# sch1.net
KiCad netlist of a schematic drawn in Altium Designer
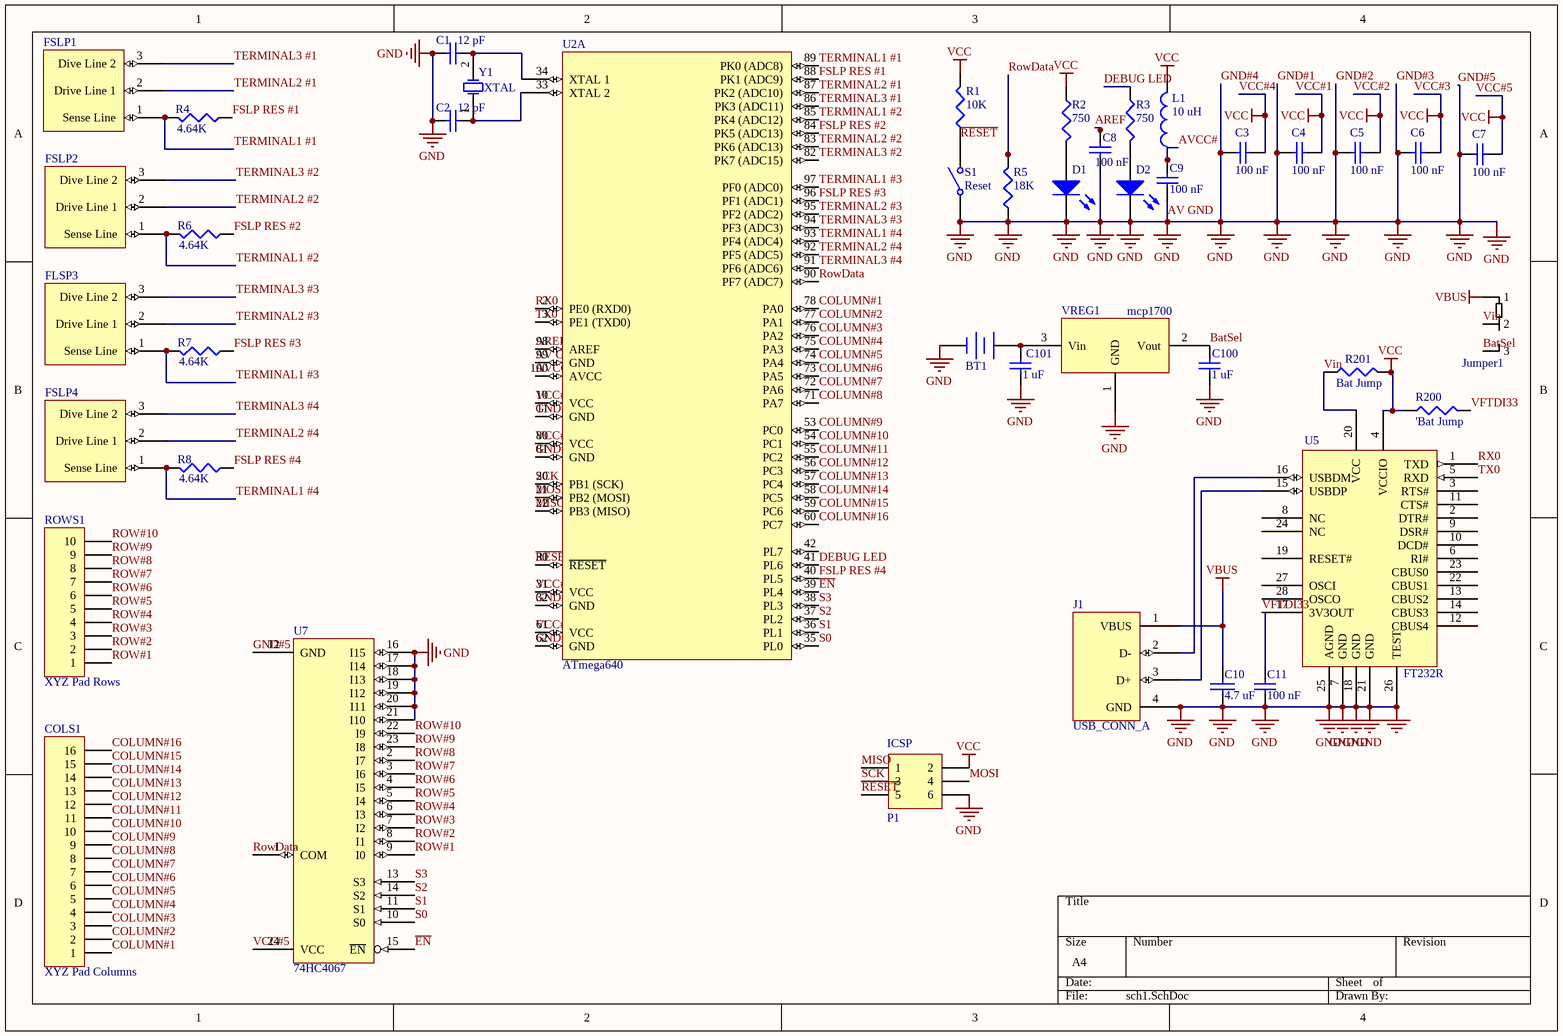
[diagram p0: sch1.SchDoc]

(export (version "E")
  (design (tool "Eeschema 10.0.6"))
  (components
    (comp (ref "BT1")
      (value "Battery 3.7V Li-Ion")
      (footprint "BAT-2")
      (description "Multicell Battery")
      (fields (field (name "PUBLISHER") "Altium Limited"))
      (libsource (lib "Miscellaneous Devices") (part "Battery"))
    )
    (comp (ref "C1")
      (value "12 pF")
      (footprint "0805")
      (description "Capacitor")
      (fields (field (name "PART NUMBER") "311-1100-1-ND") (field (name "MANUFACTURER") "Yageo"))
      (libsource (lib "Miscellaneous Devices") (part "Cap"))
    )
    (comp (ref "C2")
      (value "12 pF")
      (footprint "0805")
      (description "Capacitor")
      (fields (field (name "PART NUMBER") "311-1100-1-ND") (field (name "MANUFACTURER") "Yageo"))
      (libsource (lib "Miscellaneous Devices") (part "Cap"))
    )
    (comp (ref "C3")
      (value "100 nF")
      (footprint "1608[0603]")
      (description "Capacitor")
      (fields (field (name "PART NUMBER") "311-1088-1-ND") (field (name "MANUFACTURER") "Yageo"))
      (libsource (lib "Miscellaneous Devices") (part "Cap"))
    )
    (comp (ref "C4")
      (value "100 nF")
      (footprint "1608[0603]")
      (description "Capacitor")
      (fields (field (name "PART NUMBER") "311-1088-1-ND") (field (name "MANUFACTURER") "Yageo"))
      (libsource (lib "Miscellaneous Devices") (part "Cap"))
    )
    (comp (ref "C5")
      (value "100 nF")
      (footprint "1608[0603]")
      (description "Capacitor")
      (fields (field (name "PART NUMBER") "311-1088-1-ND") (field (name "MANUFACTURER") "Yageo"))
      (libsource (lib "Miscellaneous Devices") (part "Cap"))
    )
    (comp (ref "C6")
      (value "100 nF")
      (footprint "1608[0603]")
      (description "Capacitor")
      (fields (field (name "PART NUMBER") "311-1088-1-ND") (field (name "MANUFACTURER") "Yageo"))
      (libsource (lib "Miscellaneous Devices") (part "Cap"))
    )
    (comp (ref "C7")
      (value "100 nF")
      (footprint "1608[0603]")
      (description "Capacitor")
      (fields (field (name "PART NUMBER") "311-1088-1-ND") (field (name "MANUFACTURER") "Yageo"))
      (libsource (lib "Miscellaneous Devices") (part "Cap"))
    )
    (comp (ref "C8")
      (value "100 nF")
      (footprint "1608[0603]")
      (description "Capacitor")
      (fields (field (name "PART NUMBER") "311-1088-1-ND") (field (name "MANUFACTURER") "Yageo"))
      (libsource (lib "Miscellaneous Devices") (part "Cap"))
    )
    (comp (ref "C9")
      (value "100 nF")
      (footprint "1608[0603]")
      (description "Capacitor")
      (fields (field (name "PART NUMBER") "311-1088-1-ND") (field (name "MANUFACTURER") "Yageo"))
      (libsource (lib "Miscellaneous Devices") (part "Cap"))
    )
    (comp (ref "C10")
      (value "4.7 uF")
      (footprint "1608[0603]")
      (description "Capacitor")
      (fields (field (name "PART NUMBER") "311-1521-1-ND"))
      (libsource (lib "*") (part "CAP"))
    )
    (comp (ref "C11")
      (value "100 nF")
      (footprint "1608[0603]")
      (description "Capacitor")
      (fields (field (name "PART NUMBER") "311-1088-1-ND") (field (name "MANUFACTURER") "Yageo"))
      (libsource (lib "Miscellaneous Devices") (part "Cap"))
    )
    (comp (ref "C100")
      (value "1 uF")
      (footprint "0805")
      (description "Capacitor")
      (libsource (lib "Miscellaneous Devices") (part "Cap"))
    )
    (comp (ref "C101")
      (value "1 uF")
      (footprint "0805")
      (description "Capacitor")
      (libsource (lib "Miscellaneous Devices") (part "Cap"))
    )
    (comp (ref "COLS1")
      (value "XYZ Pad Columns")
      (footprint "16 pin head")
      (description "Header, 16-Pin")
      (libsource (lib "Miscellaneous Connectors") (part "Header 16"))
    )
    (comp (ref "D1")
      (value "Power LED")
      (footprint "1608[0603]")
      (description "Orange")
      (fields (field (name "PART NUMBER") "475-2740-1-ND"))
      (libsource (lib "Miscellaneous Devices") (part "LED3"))
    )
    (comp (ref "D2")
      (value "Debug LED")
      (footprint "1608[0603]")
      (description "Orange")
      (fields (field (name "PART NUMBER") "475-1196-1-ND"))
      (libsource (lib "Miscellaneous Devices") (part "LED3"))
    )
    (comp (ref "FLSP3")
      (value "FSLP")
      (footprint "FSLP SMT connector")
      (fields (field (name "MANUFACTURER") "Interlink Electronics") (field (name "PART NUMBER") "34-00003"))
      (libsource (lib "FSLP schilib") (part "FSLP"))
    )
    (comp (ref "FSLP1")
      (value "FSLP")
      (footprint "FSLP SMT connector")
      (fields (field (name "MANUFACTURER") "Interlink Electronics") (field (name "PART NUMBER") "34-00003"))
      (libsource (lib "FSLP schilib") (part "FSLP"))
    )
    (comp (ref "FSLP2")
      (value "FSLP")
      (footprint "FSLP SMT connector")
      (fields (field (name "MANUFACTURER") "Interlink Electronics") (field (name "PART NUMBER") "34-00003"))
      (libsource (lib "FSLP schilib") (part "FSLP"))
    )
    (comp (ref "FSLP4")
      (value "FSLP")
      (footprint "FSLP SMT connector")
      (fields (field (name "MANUFACTURER") "Interlink Electronics") (field (name "PART NUMBER") "34-00003"))
      (libsource (lib "FSLP schilib") (part "FSLP"))
    )
    (comp (ref "J1")
      (value "USB_CONN_A")
      (footprint "USB_CONN_TYPEA_.9")
      (description "Connector USB Type A")
      (libsource (lib "*") (part "USB_CONN_A"))
    )
    (comp (ref "Jumper1")
      (value "0-Ohm Jumper 0603")
      (footprint "0603-Jumper")
      (libsource (lib "JennicNodeLib") (part "0-Ohm Jumper 0603"))
    )
    (comp (ref "L1")
      (value "10 uH")
      (footprint "1608[0603]")
      (description "AVCC filter")
      (fields (field (name "PART NUMBER") "445-6755-1-ND"))
      (libsource (lib "Miscellaneous Devices") (part "Inductor"))
    )
    (comp (ref "P1")
      (value "ICSP")
      (footprint "HDR2X3H")
      (description "Header, 3-Pin, Dual row, Right Angle")
      (libsource (lib "Miscellaneous Connectors") (part "Header 3X2H"))
    )
    (comp (ref "R1")
      (value "10K")
      (footprint "1608[0603]")
      (description "Resistor")
      (fields
        (field (name "PART NUMBER") "1276-3485-1-ND")
        (field (name "MANUFACTURER") "Samsung Electro-Mechanics America, Inc")
      )
      (libsource (lib "Miscellaneous Devices") (part "Res3"))
    )
    (comp (ref "R2")
      (value "750")
      (footprint "1608[0603]")
      (description "Resistor")
      (fields
        (field (name "PART NUMBER") "1276-4635-1-ND")
        (field (name "MANUFACTURER") "Samsung Electro-Mechanics America, Inc")
      )
      (libsource (lib "Miscellaneous Devices") (part "Res3"))
    )
    (comp (ref "R3")
      (value "750")
      (footprint "1608[0603]")
      (description "Resistor")
      (fields
        (field (name "PART NUMBER") "1276-4635-1-ND")
        (field (name "MANUFACTURER") "Samsung Electro-Mechanics America, Inc")
      )
      (libsource (lib "Miscellaneous Devices") (part "Res3"))
    )
    (comp (ref "R4")
      (value "4.64K")
      (footprint "1608[0603]")
      (description "Resistor")
      (fields
        (field (name "PART NUMBER") "1276-4709-1-ND")
        (field (name "MANUFACTURER") "Samsung Electro-Mechanics America, Inc")
      )
      (libsource (lib "Miscellaneous Devices") (part "Res3"))
    )
    (comp (ref "R5")
      (value "18K")
      (footprint "1608[0603]")
      (description "Resistor")
      (fields
        (field (name "PART NUMBER") "1276-4768-1-ND")
        (field (name "MANUFACTURER") "Samsung Electro-Mechanics America, Inc")
      )
      (libsource (lib "Miscellaneous Devices") (part "Res3"))
    )
    (comp (ref "R6")
      (value "4.64K")
      (footprint "1608[0603]")
      (description "Resistor")
      (fields
        (field (name "PART NUMBER") "1276-4709-1-ND")
        (field (name "MANUFACTURER") "Samsung Electro-Mechanics America, Inc")
      )
      (libsource (lib "Miscellaneous Devices") (part "Res3"))
    )
    (comp (ref "R7")
      (value "4.64K")
      (footprint "1608[0603]")
      (description "Resistor")
      (fields
        (field (name "PART NUMBER") "1276-4709-1-ND")
        (field (name "MANUFACTURER") "Samsung Electro-Mechanics America, Inc")
      )
      (libsource (lib "Miscellaneous Devices") (part "Res3"))
    )
    (comp (ref "R8")
      (value "4.64K")
      (footprint "1608[0603]")
      (description "Resistor")
      (fields
        (field (name "PART NUMBER") "1276-4709-1-ND")
        (field (name "MANUFACTURER") "Samsung Electro-Mechanics America, Inc")
      )
      (libsource (lib "Miscellaneous Devices") (part "Res3"))
    )
    (comp (ref "R200")
      (value "'Bat Jump")
      (footprint "J1-0603")
      (description "Resistor")
      (libsource (lib "Miscellaneous Devices") (part "Res3"))
    )
    (comp (ref "R201")
      (value "Bat Jump")
      (footprint "J1-0603")
      (description "Resistor")
      (libsource (lib "Miscellaneous Devices") (part "Res3"))
    )
    (comp (ref "ROWS1")
      (value "XYZ Pad Rows")
      (footprint "10 pin Head")
      (description "Header, 10-Pin")
      (libsource (lib "Miscellaneous Connectors") (part "Header 10"))
    )
    (comp (ref "S1")
      (value "Reset")
      (footprint "B3U-1000P")
      (description "Single-Pole, Single-Throw Switch")
      (fields (field (name "PART NUMBER") "SW1020CT-ND"))
      (libsource (lib "Miscellaneous Devices") (part "SW-SPST"))
    )
    (comp (ref "U2")
      (value "ATmega640")
      (footprint "100A_N")
      (fields (field (name "PART NUMBER") "ATMEGA640-16AURCT-ND"))
      (libsource (lib "Atmel Microcontroller 8-16-Bit AVR XMEGA") (part "ATxmega64A1-AU"))
    )
    (comp (ref "U5")
      (value "FT232R")
      (footprint "SSOP28")
      (description "FT232R - USB UART IC")
      (libsource (lib "*") (part "FT232R"))
    )
    (comp (ref "U7")
      (value "74HC4067")
      (footprint "74HC4067")
      (description "MUX-74HC4067")
      (fields (field (name "PART NUMBER") "568-2699-5-ND") (field (name "MANUFACTURER") "NXP"))
      (libsource (lib "multiplexer New") (part "MUX-74HC4067"))
    )
    (comp (ref "VREG1")
      (value "mcp1700")
      (footprint "SOT-23")
      (libsource (lib "FSLP schilib") (part "mcp1700"))
    )
    (comp (ref "Y1")
      (value "XTAL")
      (footprint "crystal")
      (description "Crystal Oscillator")
      (fields (field (name "PART NUMBER") "644-1204-1-ND"))
      (libsource (lib "Miscellaneous Devices") (part "XTAL"))
    )
  )
  (nets
    (net (code "1") (name "/AREF") (class "Default")
      (node (ref "C8") (pin "2") (pinfunction "2_2") (pintype "passive"))
      (node (ref "U2") (pin "98") (pinfunction "AREF_98") (pintype "bidirectional"))
    )
    (net (code "2") (name "/AVCC#") (class "Default")
      (node (ref "C9") (pin "2") (pinfunction "2_2") (pintype "passive"))
      (node (ref "L1") (pin "1") (pinfunction "1_1") (pintype "passive"))
      (node (ref "U2") (pin "100") (pinfunction "AVCC_100") (pintype "bidirectional"))
    )
    (net (code "3") (name "/BatSel") (class "Default")
      (node (ref "C100") (pin "2") (pinfunction "2_2") (pintype "passive"))
      (node (ref "Jumper1") (pin "3") (pinfunction "3_3") (pintype "passive"))
      (node (ref "VREG1") (pin "2") (pinfunction "Vout_2") (pintype "power_in"))
    )
    (net (code "4") (name "/COLUMN#1") (class "Default")
      (node (ref "COLS1") (pin "1") (pinfunction "1_1") (pintype "passive"))
      (node (ref "U2") (pin "78") (pinfunction "PA0_78") (pintype "bidirectional"))
    )
    (net (code "5") (name "/COLUMN#2") (class "Default")
      (node (ref "COLS1") (pin "2") (pinfunction "2_2") (pintype "passive"))
      (node (ref "U2") (pin "77") (pinfunction "PA1_77") (pintype "bidirectional"))
    )
    (net (code "6") (name "/COLUMN#3") (class "Default")
      (node (ref "COLS1") (pin "3") (pinfunction "3_3") (pintype "passive"))
      (node (ref "U2") (pin "76") (pinfunction "PA2_76") (pintype "bidirectional"))
    )
    (net (code "7") (name "/COLUMN#4") (class "Default")
      (node (ref "COLS1") (pin "4") (pinfunction "4_4") (pintype "passive"))
      (node (ref "U2") (pin "75") (pinfunction "PA3_75") (pintype "bidirectional"))
    )
    (net (code "8") (name "/COLUMN#5") (class "Default")
      (node (ref "COLS1") (pin "5") (pinfunction "5_5") (pintype "passive"))
      (node (ref "U2") (pin "74") (pinfunction "PA4_74") (pintype "bidirectional"))
    )
    (net (code "9") (name "/COLUMN#6") (class "Default")
      (node (ref "COLS1") (pin "6") (pinfunction "6_6") (pintype "passive"))
      (node (ref "U2") (pin "73") (pinfunction "PA5_73") (pintype "bidirectional"))
    )
    (net (code "10") (name "/COLUMN#7") (class "Default")
      (node (ref "COLS1") (pin "7") (pinfunction "7_7") (pintype "passive"))
      (node (ref "U2") (pin "72") (pinfunction "PA6_72") (pintype "bidirectional"))
    )
    (net (code "11") (name "/COLUMN#8") (class "Default")
      (node (ref "COLS1") (pin "8") (pinfunction "8_8") (pintype "passive"))
      (node (ref "U2") (pin "71") (pinfunction "PA7_71") (pintype "bidirectional"))
    )
    (net (code "12") (name "/COLUMN#9") (class "Default")
      (node (ref "COLS1") (pin "9") (pinfunction "9_9") (pintype "passive"))
      (node (ref "U2") (pin "53") (pinfunction "PC0_53") (pintype "bidirectional"))
    )
    (net (code "13") (name "/COLUMN#10") (class "Default")
      (node (ref "COLS1") (pin "10") (pinfunction "10_10") (pintype "passive"))
      (node (ref "U2") (pin "54") (pinfunction "PC1_54") (pintype "bidirectional"))
    )
    (net (code "14") (name "/COLUMN#11") (class "Default")
      (node (ref "COLS1") (pin "11") (pinfunction "11_11") (pintype "passive"))
      (node (ref "U2") (pin "55") (pinfunction "PC2_55") (pintype "bidirectional"))
    )
    (net (code "15") (name "/COLUMN#12") (class "Default")
      (node (ref "COLS1") (pin "12") (pinfunction "12_12") (pintype "passive"))
      (node (ref "U2") (pin "56") (pinfunction "PC3_56") (pintype "bidirectional"))
    )
    (net (code "16") (name "/COLUMN#13") (class "Default")
      (node (ref "COLS1") (pin "13") (pinfunction "13_13") (pintype "passive"))
      (node (ref "U2") (pin "57") (pinfunction "PC4_57") (pintype "bidirectional"))
    )
    (net (code "17") (name "/COLUMN#14") (class "Default")
      (node (ref "COLS1") (pin "14") (pinfunction "14_14") (pintype "passive"))
      (node (ref "U2") (pin "58") (pinfunction "PC5_58") (pintype "bidirectional"))
    )
    (net (code "18") (name "/COLUMN#15") (class "Default")
      (node (ref "COLS1") (pin "15") (pinfunction "15_15") (pintype "passive"))
      (node (ref "U2") (pin "59") (pinfunction "PC6_59") (pintype "bidirectional"))
    )
    (net (code "19") (name "/COLUMN#16") (class "Default")
      (node (ref "COLS1") (pin "16") (pinfunction "16_16") (pintype "passive"))
      (node (ref "U2") (pin "60") (pinfunction "PC7_60") (pintype "bidirectional"))
    )
    (net (code "20") (name "/DEBUG LED") (class "Default")
      (node (ref "R3") (pin "1") (pinfunction "1_1") (pintype "passive"))
      (node (ref "U2") (pin "41") (pinfunction "PL6_41") (pintype "bidirectional"))
    )
    (net (code "21") (name "/FSLP RES #1") (class "Default")
      (node (ref "R4") (pin "1") (pinfunction "1_1") (pintype "passive"))
      (node (ref "U2") (pin "88") (pinfunction "PK1_(ADC9)_88") (pintype "bidirectional"))
    )
    (net (code "22") (name "/FSLP RES #2") (class "Default")
      (node (ref "R6") (pin "1") (pinfunction "1_1") (pintype "passive"))
      (node (ref "U2") (pin "84") (pinfunction "PK5_(ADC13)_84") (pintype "bidirectional"))
    )
    (net (code "23") (name "/FSLP RES #3") (class "Default")
      (node (ref "R7") (pin "1") (pinfunction "1_1") (pintype "passive"))
      (node (ref "U2") (pin "96") (pinfunction "PF1_(ADC1)_96") (pintype "bidirectional"))
    )
    (net (code "24") (name "/FSLP RES #4") (class "Default")
      (node (ref "R8") (pin "1") (pinfunction "1_1") (pintype "passive"))
      (node (ref "U2") (pin "40") (pinfunction "PL5_40") (pintype "bidirectional"))
    )
    (net (code "25") (name "/MISO") (class "Default")
      (node (ref "P1") (pin "1") (pinfunction "1_1") (pintype "passive"))
      (node (ref "U2") (pin "22") (pinfunction "PB3_(MISO)_22") (pintype "bidirectional"))
    )
    (net (code "26") (name "/MOSI") (class "Default")
      (node (ref "P1") (pin "4") (pinfunction "4_4") (pintype "passive"))
      (node (ref "U2") (pin "21") (pinfunction "PB2_(MOSI)_21") (pintype "bidirectional"))
    )
    (net (code "27") (name "/ROW#1") (class "Default")
      (node (ref "ROWS1") (pin "1") (pinfunction "1_1") (pintype "passive"))
      (node (ref "U7") (pin "9") (pinfunction "I0_9") (pintype "bidirectional"))
    )
    (net (code "28") (name "/ROW#2") (class "Default")
      (node (ref "ROWS1") (pin "2") (pinfunction "2_2") (pintype "passive"))
      (node (ref "U7") (pin "8") (pinfunction "I1_8") (pintype "bidirectional"))
    )
    (net (code "29") (name "/ROW#3") (class "Default")
      (node (ref "ROWS1") (pin "3") (pinfunction "3_3") (pintype "passive"))
      (node (ref "U7") (pin "7") (pinfunction "I2_7") (pintype "bidirectional"))
    )
    (net (code "30") (name "/ROW#4") (class "Default")
      (node (ref "ROWS1") (pin "4") (pinfunction "4_4") (pintype "passive"))
      (node (ref "U7") (pin "6") (pinfunction "I3_6") (pintype "bidirectional"))
    )
    (net (code "31") (name "/ROW#5") (class "Default")
      (node (ref "ROWS1") (pin "5") (pinfunction "5_5") (pintype "passive"))
      (node (ref "U7") (pin "5") (pinfunction "I4_5") (pintype "bidirectional"))
    )
    (net (code "32") (name "/ROW#6") (class "Default")
      (node (ref "ROWS1") (pin "6") (pinfunction "6_6") (pintype "passive"))
      (node (ref "U7") (pin "4") (pinfunction "I5_4") (pintype "bidirectional"))
    )
    (net (code "33") (name "/ROW#7") (class "Default")
      (node (ref "ROWS1") (pin "7") (pinfunction "7_7") (pintype "passive"))
      (node (ref "U7") (pin "3") (pinfunction "I6_3") (pintype "bidirectional"))
    )
    (net (code "34") (name "/ROW#8") (class "Default")
      (node (ref "ROWS1") (pin "8") (pinfunction "8_8") (pintype "passive"))
      (node (ref "U7") (pin "2") (pinfunction "I7_2") (pintype "bidirectional"))
    )
    (net (code "35") (name "/ROW#9") (class "Default")
      (node (ref "ROWS1") (pin "9") (pinfunction "9_9") (pintype "passive"))
      (node (ref "U7") (pin "23") (pinfunction "I8_23") (pintype "bidirectional"))
    )
    (net (code "36") (name "/ROW#10") (class "Default")
      (node (ref "ROWS1") (pin "10") (pinfunction "10_10") (pintype "passive"))
      (node (ref "U7") (pin "22") (pinfunction "I9_22") (pintype "bidirectional"))
    )
    (net (code "37") (name "/RX0") (class "Default")
      (node (ref "U2") (pin "2") (pinfunction "PE0_(RXD0)_2") (pintype "bidirectional"))
      (node (ref "U5") (pin "1") (pinfunction "TXD_1") (pintype "output"))
    )
    (net (code "38") (name "/RowData") (class "Default")
      (node (ref "R5") (pin "2") (pinfunction "2_2") (pintype "passive"))
      (node (ref "U2") (pin "90") (pinfunction "PF7_(ADC7)_90") (pintype "bidirectional"))
      (node (ref "U7") (pin "1") (pinfunction "COM_1") (pintype "bidirectional"))
    )
    (net (code "39") (name "/S0") (class "Default")
      (node (ref "U2") (pin "35") (pinfunction "PL0_35") (pintype "bidirectional"))
      (node (ref "U7") (pin "10") (pinfunction "S0_10") (pintype "input"))
    )
    (net (code "40") (name "/S1") (class "Default")
      (node (ref "U2") (pin "36") (pinfunction "PL1_36") (pintype "bidirectional"))
      (node (ref "U7") (pin "11") (pinfunction "S1_11") (pintype "input"))
    )
    (net (code "41") (name "/S2") (class "Default")
      (node (ref "U2") (pin "37") (pinfunction "PL2_37") (pintype "bidirectional"))
      (node (ref "U7") (pin "14") (pinfunction "S2_14") (pintype "input"))
    )
    (net (code "42") (name "/S3") (class "Default")
      (node (ref "U2") (pin "38") (pinfunction "PL3_38") (pintype "bidirectional"))
      (node (ref "U7") (pin "13") (pinfunction "S3_13") (pintype "input"))
    )
    (net (code "43") (name "/SCK") (class "Default")
      (node (ref "P1") (pin "3") (pinfunction "3_3") (pintype "passive"))
      (node (ref "U2") (pin "20") (pinfunction "PB1_(SCK)_20") (pintype "bidirectional"))
    )
    (net (code "44") (name "/TERMINAL1 #1") (class "Default")
      (node (ref "FSLP1") (pin "1") (pinfunction "Sense_Line_1") (pintype "bidirectional"))
      (node (ref "R4") (pin "2") (pinfunction "2_2") (pintype "passive"))
      (node (ref "U2") (pin "89") (pinfunction "PK0_(ADC8)_89") (pintype "bidirectional"))
    )
    (net (code "45") (name "/TERMINAL1 #2") (class "Default")
      (node (ref "FSLP2") (pin "1") (pinfunction "Sense_Line_1") (pintype "bidirectional"))
      (node (ref "R6") (pin "2") (pinfunction "2_2") (pintype "passive"))
      (node (ref "U2") (pin "85") (pinfunction "PK4_(ADC12)_85") (pintype "bidirectional"))
    )
    (net (code "46") (name "/TERMINAL1 #3") (class "Default")
      (node (ref "FLSP3") (pin "1") (pinfunction "Sense_Line_1") (pintype "bidirectional"))
      (node (ref "R7") (pin "2") (pinfunction "2_2") (pintype "passive"))
      (node (ref "U2") (pin "97") (pinfunction "PF0_(ADC0)_97") (pintype "bidirectional"))
    )
    (net (code "47") (name "/TERMINAL1 #4") (class "Default")
      (node (ref "FSLP4") (pin "1") (pinfunction "Sense_Line_1") (pintype "bidirectional"))
      (node (ref "R8") (pin "2") (pinfunction "2_2") (pintype "passive"))
      (node (ref "U2") (pin "93") (pinfunction "PF4_(ADC4)_93") (pintype "bidirectional"))
    )
    (net (code "48") (name "/TERMINAL2 #1") (class "Default")
      (node (ref "FSLP1") (pin "2") (pinfunction "Drive_Line_1_2") (pintype "bidirectional"))
      (node (ref "U2") (pin "87") (pinfunction "PK2_(ADC10)_87") (pintype "bidirectional"))
    )
    (net (code "49") (name "/TERMINAL2 #2") (class "Default")
      (node (ref "FSLP2") (pin "2") (pinfunction "Drive_Line_1_2") (pintype "bidirectional"))
      (node (ref "U2") (pin "83") (pinfunction "PK6_(ADC13)_83") (pintype "bidirectional"))
    )
    (net (code "50") (name "/TERMINAL2 #3") (class "Default")
      (node (ref "FLSP3") (pin "2") (pinfunction "Drive_Line_1_2") (pintype "bidirectional"))
      (node (ref "U2") (pin "95") (pinfunction "PF2_(ADC2)_95") (pintype "bidirectional"))
    )
    (net (code "51") (name "/TERMINAL2 #4") (class "Default")
      (node (ref "FSLP4") (pin "2") (pinfunction "Drive_Line_1_2") (pintype "bidirectional"))
      (node (ref "U2") (pin "92") (pinfunction "PF5_(ADC5)_92") (pintype "bidirectional"))
    )
    (net (code "52") (name "/TERMINAL3 #1") (class "Default")
      (node (ref "FSLP1") (pin "3") (pinfunction "Dive_Line_2_3") (pintype "bidirectional"))
      (node (ref "U2") (pin "86") (pinfunction "PK3_(ADC11)_86") (pintype "bidirectional"))
    )
    (net (code "53") (name "/TERMINAL3 #2") (class "Default")
      (node (ref "FSLP2") (pin "3") (pinfunction "Dive_Line_2_3") (pintype "bidirectional"))
      (node (ref "U2") (pin "82") (pinfunction "PK7_(ADC15)_82") (pintype "bidirectional"))
    )
    (net (code "54") (name "/TERMINAL3 #3") (class "Default")
      (node (ref "FLSP3") (pin "3") (pinfunction "Dive_Line_2_3") (pintype "bidirectional"))
      (node (ref "U2") (pin "94") (pinfunction "PF3_(ADC3)_94") (pintype "bidirectional"))
    )
    (net (code "55") (name "/TERMINAL3 #4") (class "Default")
      (node (ref "FSLP4") (pin "3") (pinfunction "Dive_Line_2_3") (pintype "bidirectional"))
      (node (ref "U2") (pin "91") (pinfunction "PF6_(ADC6)_91") (pintype "bidirectional"))
    )
    (net (code "56") (name "/TX0") (class "Default")
      (node (ref "U2") (pin "3") (pinfunction "PE1_(TXD0)_3") (pintype "bidirectional"))
      (node (ref "U5") (pin "5") (pinfunction "RXD_5") (pintype "input"))
    )
    (net (code "57") (name "/VFTDI33") (class "Default")
      (node (ref "C11") (pin "2") (pinfunction "2_2") (pintype "passive"))
      (node (ref "R200") (pin "2") (pinfunction "2_2") (pintype "passive"))
      (node (ref "U5") (pin "17") (pinfunction "3V3OUT_17") (pintype "power_in"))
    )
    (net (code "58") (name "/Vin") (class "Default")
      (node (ref "Jumper1") (pin "2") (pinfunction "2_2") (pintype "passive"))
      (node (ref "R201") (pin "1") (pinfunction "1_1") (pintype "passive"))
      (node (ref "U5") (pin "20") (pinfunction "VCC_20") (pintype "power_in"))
    )
    (net (code "59") (name "/~{EN}") (class "Default")
      (node (ref "U2") (pin "39") (pinfunction "PL4_39") (pintype "bidirectional"))
      (node (ref "U7") (pin "15") (pinfunction "~{EN}_15") (pintype "input"))
    )
    (net (code "60") (name "/~{RESET}") (class "Default")
      (node (ref "P1") (pin "5") (pinfunction "5_5") (pintype "passive"))
      (node (ref "R1") (pin "1") (pinfunction "1_1") (pintype "passive"))
      (node (ref "S1") (pin "2") (pinfunction "NO_2") (pintype "passive"))
      (node (ref "U2") (pin "30") (pinfunction "~{RESET}_30") (pintype "bidirectional"))
    )
    (net (code "61") (name "GND") (class "Default")
      (node (ref "BT1") (pin "2") (pinfunction "-_2") (pintype "passive"))
      (node (ref "C1") (pin "2") (pinfunction "2_2") (pintype "passive"))
      (node (ref "C10") (pin "2") (pinfunction "2_2") (pintype "passive"))
      (node (ref "C100") (pin "1") (pinfunction "1_1") (pintype "passive"))
      (node (ref "C101") (pin "1") (pinfunction "1_1") (pintype "passive"))
      (node (ref "C11") (pin "1") (pinfunction "1_1") (pintype "passive"))
      (node (ref "C2") (pin "2") (pinfunction "2_2") (pintype "passive"))
      (node (ref "C3") (pin "2") (pinfunction "2_2") (pintype "passive"))
      (node (ref "C4") (pin "2") (pinfunction "2_2") (pintype "passive"))
      (node (ref "C5") (pin "2") (pinfunction "2_2") (pintype "passive"))
      (node (ref "C6") (pin "2") (pinfunction "2_2") (pintype "passive"))
      (node (ref "C7") (pin "2") (pinfunction "2_2") (pintype "passive"))
      (node (ref "C8") (pin "1") (pinfunction "1_1") (pintype "passive"))
      (node (ref "C9") (pin "1") (pinfunction "1_1") (pintype "passive"))
      (node (ref "D1") (pin "2") (pinfunction "K_2") (pintype "passive"))
      (node (ref "D2") (pin "2") (pinfunction "K_2") (pintype "passive"))
      (node (ref "J1") (pin "4") (pinfunction "GND_4") (pintype "power_in"))
      (node (ref "P1") (pin "6") (pinfunction "6_6") (pintype "passive"))
      (node (ref "R5") (pin "1") (pinfunction "1_1") (pintype "passive"))
      (node (ref "S1") (pin "1") (pinfunction "COMMON_1") (pintype "passive"))
      (node (ref "U2") (pin "11") (pinfunction "GND_11") (pintype "bidirectional"))
      (node (ref "U2") (pin "32") (pinfunction "GND_32") (pintype "bidirectional"))
      (node (ref "U2") (pin "62") (pinfunction "GND_62") (pintype "bidirectional"))
      (node (ref "U2") (pin "81") (pinfunction "GND_81") (pintype "bidirectional"))
      (node (ref "U2") (pin "99") (pinfunction "GND_99") (pintype "bidirectional"))
      (node (ref "U5") (pin "18") (pinfunction "GND_18") (pintype "power_in"))
      (node (ref "U5") (pin "21") (pinfunction "GND_21") (pintype "power_in"))
      (node (ref "U5") (pin "25") (pinfunction "AGND_25") (pintype "power_in"))
      (node (ref "U5") (pin "26") (pinfunction "TEST_26") (pintype "passive"))
      (node (ref "U5") (pin "7") (pinfunction "GND_7") (pintype "power_in"))
      (node (ref "U7") (pin "12") (pinfunction "GND_12") (pintype "power_in"))
      (node (ref "U7") (pin "16") (pinfunction "I15_16") (pintype "bidirectional"))
      (node (ref "U7") (pin "17") (pinfunction "I14_17") (pintype "bidirectional"))
      (node (ref "U7") (pin "18") (pinfunction "I13_18") (pintype "bidirectional"))
      (node (ref "U7") (pin "19") (pinfunction "I12_19") (pintype "bidirectional"))
      (node (ref "U7") (pin "20") (pinfunction "I11_20") (pintype "bidirectional"))
      (node (ref "U7") (pin "21") (pinfunction "I10_21") (pintype "bidirectional"))
      (node (ref "VREG1") (pin "1") (pinfunction "GND_1") (pintype "power_in"))
    )
    (net (code "62") (name "Net-(BT1-+)") (class "Default")
      (node (ref "BT1") (pin "1") (pinfunction "+_1") (pintype "passive"))
      (node (ref "C101") (pin "2") (pinfunction "2_2") (pintype "passive"))
      (node (ref "VREG1") (pin "3") (pinfunction "Vin_3") (pintype "power_in"))
    )
    (net (code "63") (name "Net-(D1-A)") (class "Default")
      (node (ref "D1") (pin "1") (pinfunction "A_1") (pintype "passive"))
      (node (ref "R2") (pin "2") (pinfunction "2_2") (pintype "passive"))
    )
    (net (code "64") (name "Net-(D2-A)") (class "Default")
      (node (ref "D2") (pin "1") (pinfunction "A_1") (pintype "passive"))
      (node (ref "R3") (pin "2") (pinfunction "2_2") (pintype "passive"))
    )
    (net (code "65") (name "Net-(J1-D+)") (class "Default")
      (node (ref "J1") (pin "3") (pinfunction "D+_3") (pintype "bidirectional"))
      (node (ref "U5") (pin "15") (pinfunction "USBDP_15") (pintype "bidirectional"))
    )
    (net (code "66") (name "Net-(J1-D-)") (class "Default")
      (node (ref "J1") (pin "2") (pinfunction "D-_2") (pintype "bidirectional"))
      (node (ref "U5") (pin "16") (pinfunction "USBDM_16") (pintype "bidirectional"))
    )
    (net (code "67") (name "Net-(U2A-XTAL_1)") (class "Default")
      (node (ref "C1") (pin "1") (pinfunction "1_1") (pintype "passive"))
      (node (ref "U2") (pin "34") (pinfunction "XTAL_1_34") (pintype "bidirectional"))
      (node (ref "Y1") (pin "2") (pinfunction "OSC2_2") (pintype "passive"))
    )
    (net (code "68") (name "Net-(U2A-XTAL_2)") (class "Default")
      (node (ref "C2") (pin "1") (pinfunction "1_1") (pintype "passive"))
      (node (ref "U2") (pin "33") (pinfunction "XTAL_2_33") (pintype "bidirectional"))
      (node (ref "Y1") (pin "1") (pinfunction "OSC1_1") (pintype "passive"))
    )
    (net (code "69") (name "VBUS") (class "Default")
      (node (ref "C10") (pin "1") (pinfunction "1_1") (pintype "passive"))
      (node (ref "J1") (pin "1") (pinfunction "VBUS_1") (pintype "power_in"))
      (node (ref "Jumper1") (pin "1") (pinfunction "1_1") (pintype "passive"))
    )
    (net (code "70") (name "VCC") (class "Default")
      (node (ref "C3") (pin "1") (pinfunction "1_1") (pintype "passive"))
      (node (ref "C4") (pin "1") (pinfunction "1_1") (pintype "passive"))
      (node (ref "C5") (pin "1") (pinfunction "1_1") (pintype "passive"))
      (node (ref "C6") (pin "1") (pinfunction "1_1") (pintype "passive"))
      (node (ref "C7") (pin "1") (pinfunction "1_1") (pintype "passive"))
      (node (ref "L1") (pin "2") (pinfunction "2_2") (pintype "passive"))
      (node (ref "P1") (pin "2") (pinfunction "2_2") (pintype "passive"))
      (node (ref "R1") (pin "2") (pinfunction "2_2") (pintype "passive"))
      (node (ref "R2") (pin "1") (pinfunction "1_1") (pintype "passive"))
      (node (ref "R200") (pin "1") (pinfunction "1_1") (pintype "passive"))
      (node (ref "R201") (pin "2") (pinfunction "2_2") (pintype "passive"))
      (node (ref "U2") (pin "10") (pinfunction "VCC_10") (pintype "bidirectional"))
      (node (ref "U2") (pin "31") (pinfunction "VCC_31") (pintype "bidirectional"))
      (node (ref "U2") (pin "61") (pinfunction "VCC_61") (pintype "bidirectional"))
      (node (ref "U2") (pin "80") (pinfunction "VCC_80") (pintype "bidirectional"))
      (node (ref "U5") (pin "4") (pinfunction "VCCIO_4") (pintype "power_in"))
      (node (ref "U7") (pin "24") (pinfunction "VCC_24") (pintype "power_in"))
    )
    (net (code "71") (name "unconnected-(U2A-PL7-Pad42)") (class "Default")
      (node (ref "U2") (pin "42") (pinfunction "PL7_42") (pintype "bidirectional"))
    )
    (net (code "72") (name "unconnected-(U5-CBUS0-Pad23)") (class "Default")
      (node (ref "U5") (pin "23") (pinfunction "CBUS0_23") (pintype "passive"))
    )
    (net (code "73") (name "unconnected-(U5-CBUS1-Pad22)") (class "Default")
      (node (ref "U5") (pin "22") (pinfunction "CBUS1_22") (pintype "passive"))
    )
    (net (code "74") (name "unconnected-(U5-CBUS2-Pad13)") (class "Default")
      (node (ref "U5") (pin "13") (pinfunction "CBUS2_13") (pintype "passive"))
    )
    (net (code "75") (name "unconnected-(U5-CBUS3-Pad14)") (class "Default")
      (node (ref "U5") (pin "14") (pinfunction "CBUS3_14") (pintype "passive"))
    )
    (net (code "76") (name "unconnected-(U5-CBUS4-Pad12)") (class "Default")
      (node (ref "U5") (pin "12") (pinfunction "CBUS4_12") (pintype "passive"))
    )
    (net (code "77") (name "unconnected-(U5-CTS#-Pad11)") (class "Default")
      (node (ref "U5") (pin "11") (pinfunction "CTS#_11") (pintype "passive"))
    )
    (net (code "78") (name "unconnected-(U5-DCD#-Pad10)") (class "Default")
      (node (ref "U5") (pin "10") (pinfunction "DCD#_10") (pintype "passive"))
    )
    (net (code "79") (name "unconnected-(U5-DSR#-Pad9)") (class "Default")
      (node (ref "U5") (pin "9") (pinfunction "DSR#_9") (pintype "passive"))
    )
    (net (code "80") (name "unconnected-(U5-DTR#-Pad2)") (class "Default")
      (node (ref "U5") (pin "2") (pinfunction "DTR#_2") (pintype "passive"))
    )
    (net (code "81") (name "unconnected-(U5-NC-Pad8)") (class "Default")
      (node (ref "U5") (pin "8") (pinfunction "NC_8") (pintype "passive"))
    )
    (net (code "82") (name "unconnected-(U5-NC-Pad24)") (class "Default")
      (node (ref "U5") (pin "24") (pinfunction "NC_24") (pintype "passive"))
    )
    (net (code "83") (name "unconnected-(U5-OSCI-Pad27)") (class "Default")
      (node (ref "U5") (pin "27") (pinfunction "OSCI_27") (pintype "passive"))
    )
    (net (code "84") (name "unconnected-(U5-OSCO-Pad28)") (class "Default")
      (node (ref "U5") (pin "28") (pinfunction "OSCO_28") (pintype "passive"))
    )
    (net (code "85") (name "unconnected-(U5-RESET#-Pad19)") (class "Default")
      (node (ref "U5") (pin "19") (pinfunction "RESET#_19") (pintype "passive"))
    )
    (net (code "86") (name "unconnected-(U5-RI#-Pad6)") (class "Default")
      (node (ref "U5") (pin "6") (pinfunction "RI#_6") (pintype "passive"))
    )
    (net (code "87") (name "unconnected-(U5-RTS#-Pad3)") (class "Default")
      (node (ref "U5") (pin "3") (pinfunction "RTS#_3") (pintype "passive"))
    )
  )
)
